# Pipscat_full_color_Saintcon_Minibadge.net
KiCad netlist of a schematic drawn in EasyEDA Pro
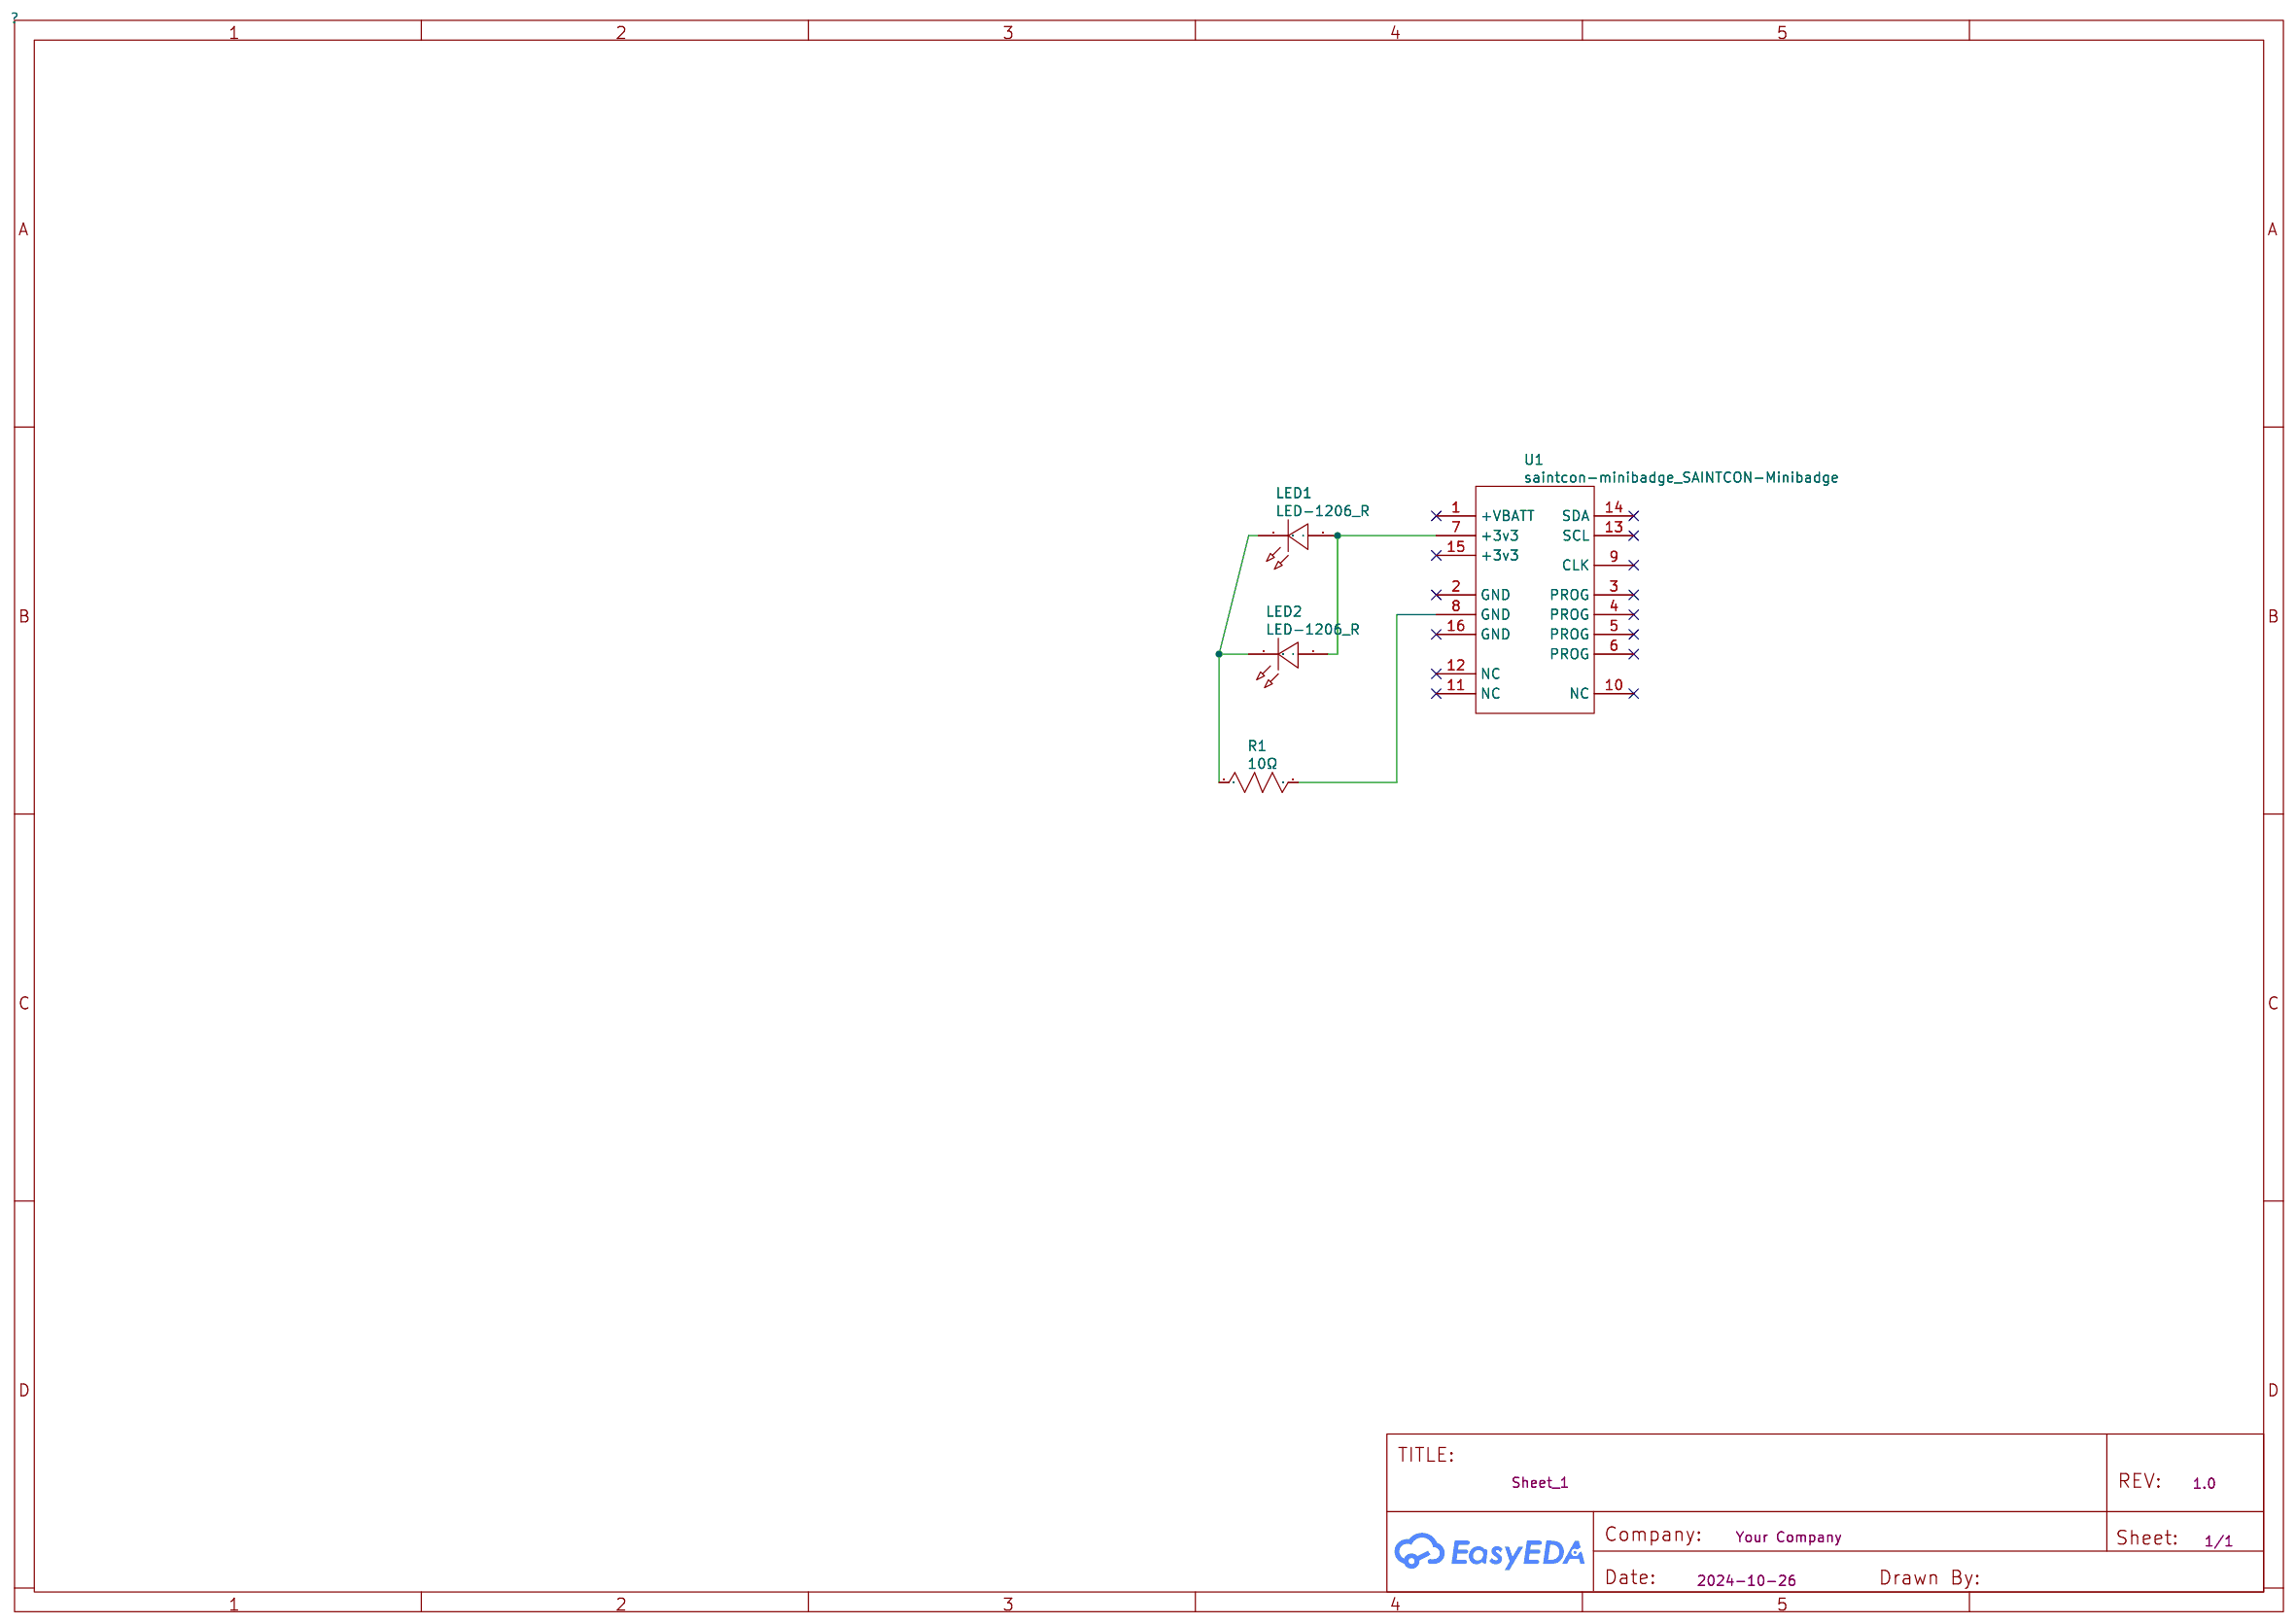
[diagram p0: schematic sheet]

(export (version "E")
  (design (tool "Eeschema 10.0.6"))
  (components
    (comp (ref "LED1")
      (value "LED-1206_R")
      (footprint "easyedapro:LED_1206")
      (libsource (lib "easyedapro") (part "LED-1206_R"))
    )
    (comp (ref "LED2")
      (value "LED-1206_R")
      (footprint "easyedapro:LED_1206")
      (libsource (lib "easyedapro") (part "LED-1206_R"))
    )
    (comp (ref "R1") (value "10Ω") (footprint "easyedapro:R1206") (libsource (lib "easyedapro") (part "10Ω")))
    (comp (ref "U1")
      (value "saintcon-minibadge_SAINTCON-Minibadge")
      (footprint "easyedapro:SAINTCON-MINIBADGE")
      (libsource (lib "easyedapro") (part "saintcon-minibadge_SAINTCON-Minibadge"))
    )
  )
  (nets
    (net (code "1") (name "Net-(LED1-1)") (class "Default")
      (node (ref "LED1") (pin "2") (pinfunction "1_2") (pintype "unspecified"))
      (node (ref "LED2") (pin "2") (pinfunction "1_2") (pintype "unspecified"))
      (node (ref "U1") (pin "7") (pinfunction "+3v3_7") (pintype "bidirectional"))
    )
    (net (code "2") (name "Net-(LED1-2)") (class "Default")
      (node (ref "LED1") (pin "1") (pinfunction "2_1") (pintype "unspecified"))
      (node (ref "LED2") (pin "1") (pinfunction "2_1") (pintype "unspecified"))
      (node (ref "R1") (pin "1") (pinfunction "1_1") (pintype "unspecified"))
    )
    (net (code "3") (name "Net-(R1-Pad2)") (class "Default")
      (node (ref "R1") (pin "2") (pinfunction "2_2") (pintype "unspecified"))
      (node (ref "U1") (pin "8") (pinfunction "GND_8") (pintype "bidirectional"))
    )
    (net (code "4") (name "unconnected-(U1-+3v3-Pad15)") (class "Default")
      (node (ref "U1") (pin "15") (pinfunction "+3v3_15") (pintype "bidirectional+no_connect"))
    )
    (net (code "5") (name "unconnected-(U1-+VBATT-Pad1)") (class "Default")
      (node (ref "U1") (pin "1") (pinfunction "+VBATT_1") (pintype "bidirectional+no_connect"))
    )
    (net (code "6") (name "unconnected-(U1-CLK-Pad9)") (class "Default")
      (node (ref "U1") (pin "9") (pinfunction "CLK_9") (pintype "output+no_connect"))
    )
    (net (code "7") (name "unconnected-(U1-GND-Pad2)") (class "Default")
      (node (ref "U1") (pin "2") (pinfunction "GND_2") (pintype "bidirectional+no_connect"))
    )
    (net (code "8") (name "unconnected-(U1-GND-Pad16)") (class "Default")
      (node (ref "U1") (pin "16") (pinfunction "GND_16") (pintype "bidirectional+no_connect"))
    )
    (net (code "9") (name "unconnected-(U1-NC-Pad10)") (class "Default")
      (node (ref "U1") (pin "10") (pinfunction "NC_10") (pintype "bidirectional+no_connect"))
    )
    (net (code "10") (name "unconnected-(U1-NC-Pad11)") (class "Default")
      (node (ref "U1") (pin "11") (pinfunction "NC_11") (pintype "bidirectional+no_connect"))
    )
    (net (code "11") (name "unconnected-(U1-NC-Pad12)") (class "Default")
      (node (ref "U1") (pin "12") (pinfunction "NC_12") (pintype "bidirectional+no_connect"))
    )
    (net (code "12") (name "unconnected-(U1-PROG-Pad3)") (class "Default")
      (node (ref "U1") (pin "3") (pinfunction "PROG_3") (pintype "bidirectional+no_connect"))
    )
    (net (code "13") (name "unconnected-(U1-PROG-Pad4)") (class "Default")
      (node (ref "U1") (pin "4") (pinfunction "PROG_4") (pintype "bidirectional+no_connect"))
    )
    (net (code "14") (name "unconnected-(U1-PROG-Pad5)") (class "Default")
      (node (ref "U1") (pin "5") (pinfunction "PROG_5") (pintype "bidirectional+no_connect"))
    )
    (net (code "15") (name "unconnected-(U1-PROG-Pad6)") (class "Default")
      (node (ref "U1") (pin "6") (pinfunction "PROG_6") (pintype "bidirectional+no_connect"))
    )
    (net (code "16") (name "unconnected-(U1-SCL-Pad13)") (class "Default")
      (node (ref "U1") (pin "13") (pinfunction "SCL_13") (pintype "output+no_connect"))
    )
    (net (code "17") (name "unconnected-(U1-SDA-Pad14)") (class "Default")
      (node (ref "U1") (pin "14") (pinfunction "SDA_14") (pintype "bidirectional+no_connect"))
    )
  )
)
